# PGA-103_VHF_UHF.net
KiCad netlist of a schematic drawn in EAGLE
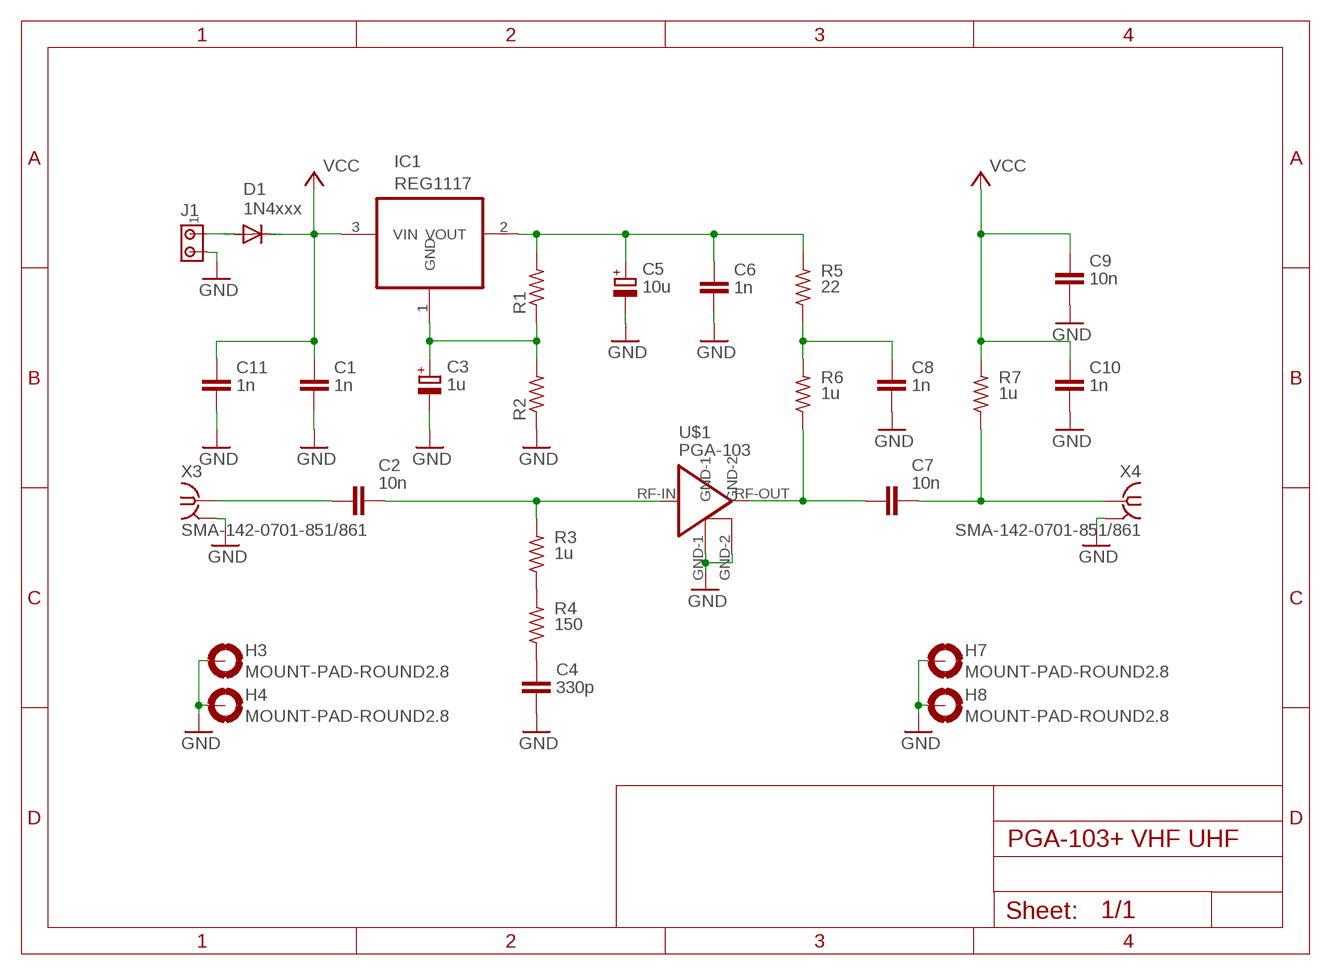
[diagram p0: schematic, sheet 1]

(export (version "E")
  (design (tool "Eeschema 10.0.6"))
  (components
    (comp (ref "C1")
      (value "1n")
      (footprint "eagle-import:C1206")
      (libsource (lib "eagle-import") (part "C-EUC1206"))
    )
    (comp (ref "C2")
      (value "10n")
      (footprint "eagle-import:C1206")
      (libsource (lib "eagle-import") (part "C-EUC1206"))
    )
    (comp (ref "C3")
      (value "1u")
      (footprint "eagle-import:CT6032")
      (libsource (lib "eagle-import") (part "CPOL-EUCT6032"))
    )
    (comp (ref "C4")
      (value "330p")
      (footprint "eagle-import:C1206")
      (libsource (lib "eagle-import") (part "C-EUC1206"))
    )
    (comp (ref "C5")
      (value "10u")
      (footprint "eagle-import:CT6032")
      (libsource (lib "eagle-import") (part "CPOL-EUCT6032"))
    )
    (comp (ref "C6")
      (value "1n")
      (footprint "eagle-import:C1206")
      (libsource (lib "eagle-import") (part "C-EUC1206"))
    )
    (comp (ref "C7")
      (value "10n")
      (footprint "eagle-import:C1206")
      (libsource (lib "eagle-import") (part "C-EUC1206"))
    )
    (comp (ref "C8")
      (value "1n")
      (footprint "eagle-import:C1206")
      (libsource (lib "eagle-import") (part "C-EUC1206"))
    )
    (comp (ref "C9")
      (value "10n")
      (footprint "eagle-import:C1206")
      (libsource (lib "eagle-import") (part "C-EUC1206"))
    )
    (comp (ref "C10")
      (value "1n")
      (footprint "eagle-import:C1206")
      (libsource (lib "eagle-import") (part "C-EUC1206"))
    )
    (comp (ref "C11")
      (value "1n")
      (footprint "eagle-import:C1206")
      (libsource (lib "eagle-import") (part "C-EUC1206"))
    )
    (comp (ref "D1")
      (value "1N4xxx")
      (footprint "eagle-import:DO35-7")
      (libsource (lib "eagle-import") (part "1N4148DO35-7"))
    )
    (comp (ref "H3")
      (value "MOUNT-PAD-ROUND2.8")
      (footprint "eagle-import:2,8-PAD")
      (libsource (lib "eagle-import") (part "MOUNT-PAD-ROUND2.8"))
    )
    (comp (ref "H4")
      (value "MOUNT-PAD-ROUND2.8")
      (footprint "eagle-import:2,8-PAD")
      (libsource (lib "eagle-import") (part "MOUNT-PAD-ROUND2.8"))
    )
    (comp (ref "H7")
      (value "MOUNT-PAD-ROUND2.8")
      (footprint "eagle-import:2,8-PAD")
      (libsource (lib "eagle-import") (part "MOUNT-PAD-ROUND2.8"))
    )
    (comp (ref "H8")
      (value "MOUNT-PAD-ROUND2.8")
      (footprint "eagle-import:2,8-PAD")
      (libsource (lib "eagle-import") (part "MOUNT-PAD-ROUND2.8"))
    )
    (comp (ref "IC1")
      (value "REG1117")
      (footprint "eagle-import:SOT223")
      (libsource (lib "eagle-import") (part "REG1117"))
    )
    (comp (ref "J1")
      (value "MTA02-156")
      (footprint "eagle-import:1X2MTA")
      (libsource (lib "eagle-import") (part "MTA02-156"))
    )
    (comp (ref "R1")
      (value "R-US_M1206")
      (footprint "eagle-import:M1206")
      (libsource (lib "eagle-import") (part "R-US_M1206"))
    )
    (comp (ref "R2")
      (value "R-US_M1206")
      (footprint "eagle-import:M1206")
      (libsource (lib "eagle-import") (part "R-US_M1206"))
    )
    (comp (ref "R3")
      (value "1u")
      (footprint "eagle-import:M1206")
      (libsource (lib "eagle-import") (part "R-US_M1206"))
    )
    (comp (ref "R4")
      (value "150")
      (footprint "eagle-import:M1206")
      (libsource (lib "eagle-import") (part "R-US_M1206"))
    )
    (comp (ref "R5")
      (value "22")
      (footprint "eagle-import:M1206")
      (libsource (lib "eagle-import") (part "R-US_M1206"))
    )
    (comp (ref "R6")
      (value "1u")
      (footprint "eagle-import:M1206")
      (libsource (lib "eagle-import") (part "R-US_M1206"))
    )
    (comp (ref "R7")
      (value "1u")
      (footprint "eagle-import:M1206")
      (libsource (lib "eagle-import") (part "R-US_M1206"))
    )
    (comp (ref "U$1")
      (value "PGA-103")
      (footprint "eagle-import:DF782")
      (libsource (lib "eagle-import") (part "PGA-103"))
    )
    (comp (ref "X3")
      (value "SMA-142-0701-851/861")
      (footprint "eagle-import:J502-ND-142-0701-851_861")
      (fields (field (name "MF") "JOHNSON COMPONENTS") (field (name "MPN") "142-0701-851"))
      (libsource (lib "eagle-import") (part "SMA-142-0701-851/861"))
    )
    (comp (ref "X4")
      (value "SMA-142-0701-851/861")
      (footprint "eagle-import:J502-ND-142-0701-851_861")
      (fields (field (name "MF") "JOHNSON COMPONENTS") (field (name "MPN") "142-0701-851"))
      (libsource (lib "eagle-import") (part "SMA-142-0701-851/861"))
    )
  )
  (nets
    (net (code "1") (name "GND") (class "Default")
      (node (ref "C1") (pin "2") (pinfunction "2_2") (pintype "passive"))
      (node (ref "C10") (pin "1") (pinfunction "1_1") (pintype "passive"))
      (node (ref "C11") (pin "2") (pinfunction "2_2") (pintype "passive"))
      (node (ref "C3") (pin "-") (pinfunction "-_-") (pintype "passive"))
      (node (ref "C4") (pin "1") (pinfunction "1_1") (pintype "passive"))
      (node (ref "C5") (pin "-") (pinfunction "-_-") (pintype "passive"))
      (node (ref "C6") (pin "2") (pinfunction "2_2") (pintype "passive"))
      (node (ref "C8") (pin "1") (pinfunction "1_1") (pintype "passive"))
      (node (ref "C9") (pin "1") (pinfunction "1_1") (pintype "passive"))
      (node (ref "H3") (pin "B2,8") (pinfunction "MOUNT_B2,8") (pintype "passive"))
      (node (ref "H4") (pin "B2,8") (pinfunction "MOUNT_B2,8") (pintype "passive"))
      (node (ref "H7") (pin "B2,8") (pinfunction "MOUNT_B2,8") (pintype "passive"))
      (node (ref "H8") (pin "B2,8") (pinfunction "MOUNT_B2,8") (pintype "passive"))
      (node (ref "J1") (pin "2") (pinfunction "2_2") (pintype "passive"))
      (node (ref "R2") (pin "1") (pinfunction "1_1") (pintype "passive"))
      (node (ref "U$1") (pin "GND-1") (pinfunction "GND-1_GND-1") (pintype "power_in"))
      (node (ref "U$1") (pin "GND-2") (pinfunction "GND-2_GND-2") (pintype "power_in"))
      (node (ref "X3") (pin "G@1") (pinfunction "2_G@1") (pintype "passive"))
      (node (ref "X3") (pin "G@2") (pinfunction "2_G@2") (pintype "passive"))
      (node (ref "X3") (pin "G@3") (pinfunction "2_G@3") (pintype "passive"))
      (node (ref "X3") (pin "G@4") (pinfunction "2_G@4") (pintype "passive"))
      (node (ref "X4") (pin "G@1") (pinfunction "2_G@1") (pintype "passive"))
      (node (ref "X4") (pin "G@2") (pinfunction "2_G@2") (pintype "passive"))
      (node (ref "X4") (pin "G@3") (pinfunction "2_G@3") (pintype "passive"))
      (node (ref "X4") (pin "G@4") (pinfunction "2_G@4") (pintype "passive"))
    )
    (net (code "2") (name "Net-(C2-Pad1)") (class "Default")
      (node (ref "C2") (pin "1") (pinfunction "1_1") (pintype "passive"))
      (node (ref "X3") (pin "1") (pinfunction "1_1") (pintype "passive"))
    )
    (net (code "3") (name "Net-(C2-Pad2)") (class "Default")
      (node (ref "C2") (pin "2") (pinfunction "2_2") (pintype "passive"))
      (node (ref "R3") (pin "2") (pinfunction "2_2") (pintype "passive"))
      (node (ref "U$1") (pin "RF-IN") (pinfunction "RF-IN_RF-IN") (pintype "input"))
    )
    (net (code "4") (name "Net-(C4-Pad2)") (class "Default")
      (node (ref "C4") (pin "2") (pinfunction "2_2") (pintype "passive"))
      (node (ref "R4") (pin "1") (pinfunction "1_1") (pintype "passive"))
    )
    (net (code "5") (name "Net-(C7-Pad1)") (class "Default")
      (node (ref "C7") (pin "1") (pinfunction "1_1") (pintype "passive"))
      (node (ref "R6") (pin "1") (pinfunction "1_1") (pintype "passive"))
      (node (ref "U$1") (pin "RF-OUT") (pinfunction "RF-OUT_RF-OUT") (pintype "output"))
    )
    (net (code "6") (name "Net-(C7-Pad2)") (class "Default")
      (node (ref "C7") (pin "2") (pinfunction "2_2") (pintype "passive"))
      (node (ref "R7") (pin "1") (pinfunction "1_1") (pintype "passive"))
      (node (ref "X4") (pin "1") (pinfunction "1_1") (pintype "passive"))
    )
    (net (code "7") (name "Net-(C8-Pad2)") (class "Default")
      (node (ref "C8") (pin "2") (pinfunction "2_2") (pintype "passive"))
      (node (ref "R5") (pin "1") (pinfunction "1_1") (pintype "passive"))
      (node (ref "R6") (pin "2") (pinfunction "2_2") (pintype "passive"))
    )
    (net (code "8") (name "Net-(D1-PadA)") (class "Default")
      (node (ref "D1") (pin "A") (pinfunction "A_A") (pintype "passive"))
      (node (ref "J1") (pin "1") (pinfunction "1_1") (pintype "passive"))
    )
    (net (code "9") (name "Net-(IC1-GND)") (class "Default")
      (node (ref "C3") (pin "+") (pinfunction "+_+") (pintype "passive"))
      (node (ref "IC1") (pin "1") (pinfunction "GND_1") (pintype "power_in"))
      (node (ref "R1") (pin "1") (pinfunction "1_1") (pintype "passive"))
      (node (ref "R2") (pin "2") (pinfunction "2_2") (pintype "passive"))
    )
    (net (code "10") (name "Net-(IC1-VOUT)") (class "Default")
      (node (ref "C5") (pin "+") (pinfunction "+_+") (pintype "passive"))
      (node (ref "C6") (pin "1") (pinfunction "1_1") (pintype "passive"))
      (node (ref "IC1") (pin "2") (pinfunction "VOUT_2") (pintype "output"))
      (node (ref "R1") (pin "2") (pinfunction "2_2") (pintype "passive"))
      (node (ref "R5") (pin "2") (pinfunction "2_2") (pintype "passive"))
    )
    (net (code "11") (name "Net-(R3-Pad1)") (class "Default")
      (node (ref "R3") (pin "1") (pinfunction "1_1") (pintype "passive"))
      (node (ref "R4") (pin "2") (pinfunction "2_2") (pintype "passive"))
    )
    (net (code "12") (name "VCC") (class "Default")
      (node (ref "C1") (pin "1") (pinfunction "1_1") (pintype "passive"))
      (node (ref "C10") (pin "2") (pinfunction "2_2") (pintype "passive"))
      (node (ref "C11") (pin "1") (pinfunction "1_1") (pintype "passive"))
      (node (ref "C9") (pin "2") (pinfunction "2_2") (pintype "passive"))
      (node (ref "D1") (pin "C") (pinfunction "C_C") (pintype "passive"))
      (node (ref "IC1") (pin "3") (pinfunction "VIN_3") (pintype "input"))
      (node (ref "R7") (pin "2") (pinfunction "2_2") (pintype "passive"))
    )
  )
)
